# 8051_SCH.net
KiCad netlist of a schematic drawn in Altium Designer
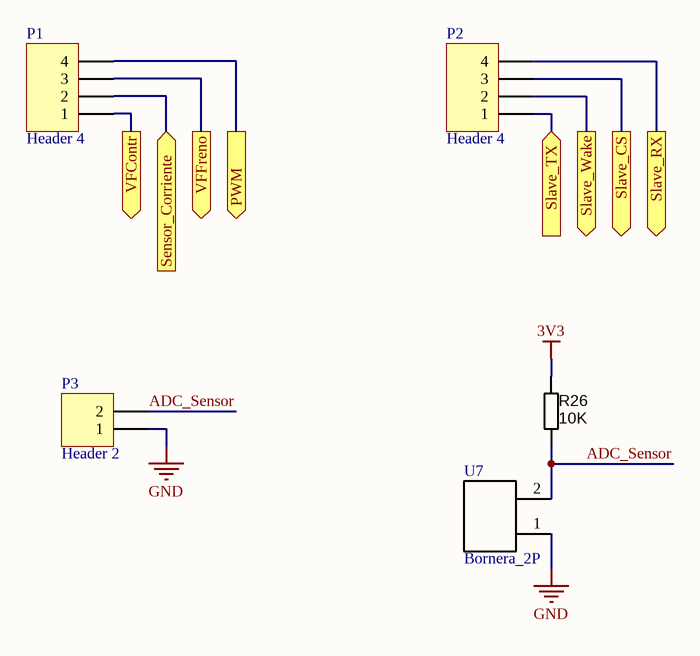
[diagram p0: 8051_SCH.SchDoc]

(export (version "E")
  (design (tool "Eeschema 10.0.6"))
  (components
    (comp (ref "P1")
      (value "Header 4")
      (footprint "HDR1X4")
      (description "Header, 4-Pin")
      (fields (field (name "PUBLISHER") "Altium Limited"))
      (libsource (lib "Miscellaneous Connectors") (part "Header 4"))
    )
    (comp (ref "P2")
      (value "Header 4")
      (footprint "HDR1X4")
      (description "Header, 4-Pin")
      (fields (field (name "PUBLISHER") "Altium Limited"))
      (libsource (lib "Miscellaneous Connectors") (part "Header 4"))
    )
    (comp (ref "P3")
      (value "Header 2")
      (footprint "HDR1X2")
      (description "Header, 2-Pin")
      (fields (field (name "PUBLISHER") "Altium Limited"))
      (libsource (lib "Miscellaneous Connectors") (part "Header 2"))
    )
    (comp (ref "R26")
      (value "10K")
      (footprint "RESC1608N_ZERO")
      (description "Resistor SMD 0603 10K 5%")
      (fields (field (name "TOLERANCE") "±5%"))
      (libsource (lib "PBL - Resistors") (part "RES_0R_0603"))
    )
    (comp (ref "U7")
      (value "Bornera_2P")
      (footprint "Bornera")
      (libsource (lib "Ampli_Lib_Sch") (part "Bornera_2P"))
    )
  )
  (nets
    (net (code "1") (name "/ADC_Sensor") (class "Default")
      (node (ref "P3") (pin "2") (pinfunction "2_2") (pintype "passive"))
      (node (ref "R26") (pin "2") (pinfunction "2_2") (pintype "passive"))
      (node (ref "U7") (pin "2") (pinfunction "2_2") (pintype "passive"))
    )
    (net (code "2") (name "/PWM") (class "Default")
      (node (ref "P1") (pin "4") (pinfunction "4_4") (pintype "passive"))
    )
    (net (code "3") (name "/Sensor_Corriente") (class "Default")
      (node (ref "P1") (pin "2") (pinfunction "2_2") (pintype "passive"))
    )
    (net (code "4") (name "/Slave_CS") (class "Default")
      (node (ref "P2") (pin "3") (pinfunction "3_3") (pintype "passive"))
    )
    (net (code "5") (name "/Slave_RX") (class "Default")
      (node (ref "P2") (pin "4") (pinfunction "4_4") (pintype "passive"))
    )
    (net (code "6") (name "/Slave_TX") (class "Default")
      (node (ref "P2") (pin "1") (pinfunction "1_1") (pintype "passive"))
    )
    (net (code "7") (name "/Slave_Wake") (class "Default")
      (node (ref "P2") (pin "2") (pinfunction "2_2") (pintype "passive"))
    )
    (net (code "8") (name "/VFContr") (class "Default")
      (node (ref "P1") (pin "1") (pinfunction "1_1") (pintype "passive"))
    )
    (net (code "9") (name "/VFFreno") (class "Default")
      (node (ref "P1") (pin "3") (pinfunction "3_3") (pintype "passive"))
    )
    (net (code "10") (name "3V3") (class "Default")
      (node (ref "R26") (pin "1") (pinfunction "1_1") (pintype "passive"))
    )
    (net (code "11") (name "GND") (class "Default")
      (node (ref "P3") (pin "1") (pinfunction "1_1") (pintype "passive"))
      (node (ref "U7") (pin "1") (pinfunction "1_1") (pintype "passive"))
    )
  )
)
